# Focuser.net
KiCad netlist of a schematic drawn in EAGLE
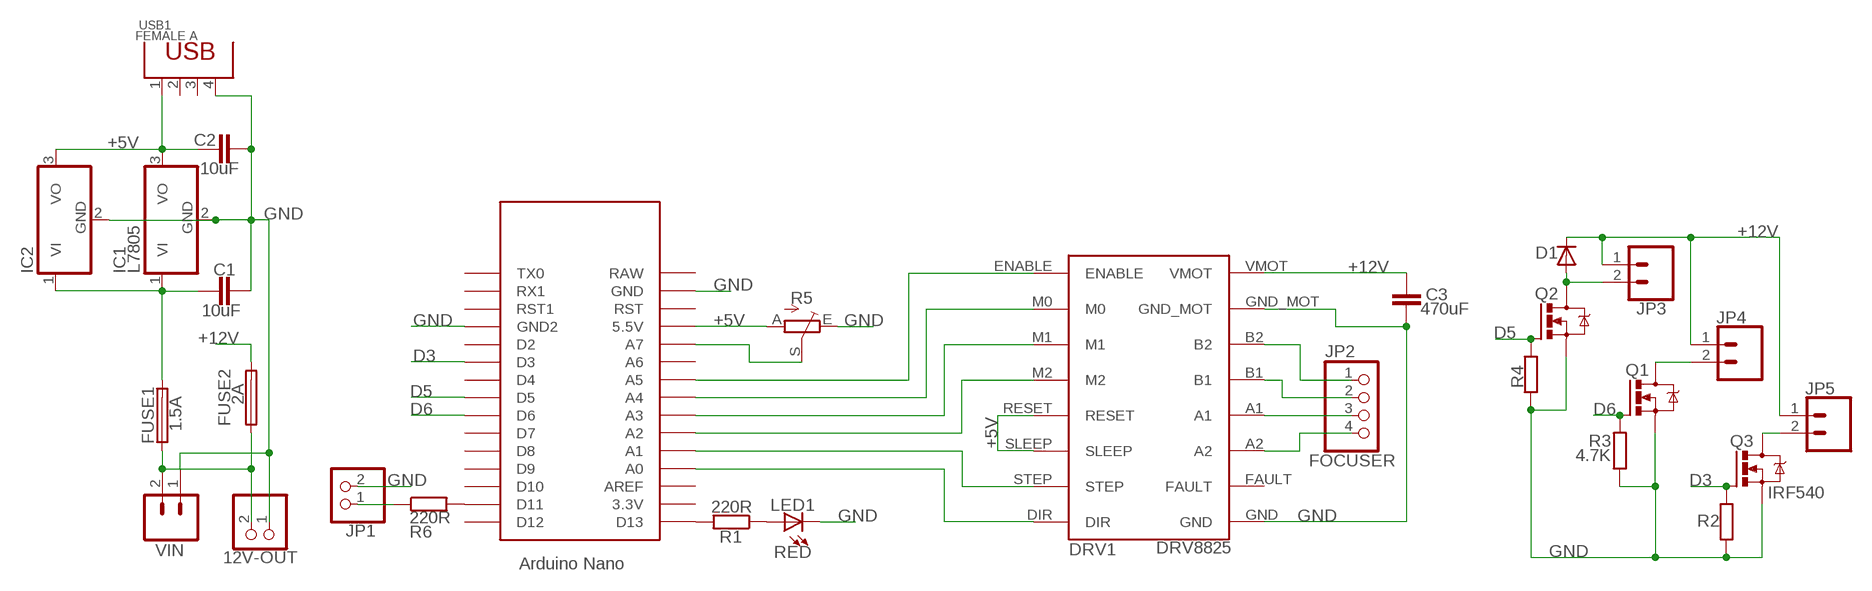
[diagram p0: schematic, sheet 1]

(export (version "E")
  (design (tool "Eeschema 10.0.6"))
  (components
    (comp (ref "12V-OUT")
      (value "PINHD-1X2")
      (footprint "eagle-import:1X02")
      (libsource (lib "eagle-import") (part "PINHD-1X2"))
    )
    (comp (ref "C1")
      (value "10uF")
      (footprint "eagle-import:C025-024X044")
      (libsource (lib "eagle-import") (part "C-EU025-024X044"))
    )
    (comp (ref "C2")
      (value "10uF")
      (footprint "eagle-import:C025-024X044")
      (libsource (lib "eagle-import") (part "C-EU025-024X044"))
    )
    (comp (ref "C3")
      (value "470uF")
      (footprint "eagle-import:C5B2.5")
      (fields (field (name "SPICEPREFIX") "C"))
      (libsource (lib "eagle-import") (part "C5/2.5"))
    )
    (comp (ref "D1")
      (value "DIODE-D-2.5")
      (footprint "eagle-import:D-2.5")
      (libsource (lib "eagle-import") (part "DIODE-D-2.5"))
    )
    (comp (ref "DRV1")
      (value "DRV8825")
      (footprint "eagle-import:DRV8825")
      (fields (field (name "SPICEPREFIX") "X"))
      (libsource (lib "eagle-import") (part "DRV8825"))
    )
    (comp (ref "FUSE1")
      (value "1.5A")
      (footprint "eagle-import:FUSE_HOLDER_5X20MM")
      (libsource (lib "eagle-import") (part "FUSEBLANK_5X20MM"))
    )
    (comp (ref "FUSE2")
      (value "2A")
      (footprint "eagle-import:FUSE_HOLDER_5X20MM")
      (libsource (lib "eagle-import") (part "FUSEBLANK_5X20MM"))
    )
    (comp (ref "IC1")
      (value "L7805")
      (footprint "eagle-import:TO220V")
      (libsource (lib "eagle-import") (part "78TV6"))
    )
    (comp (ref "IC2")
      (value "L7805")
      (footprint "eagle-import:TO220V")
      (libsource (lib "eagle-import") (part "78TV6"))
    )
    (comp (ref "JP1")
      (value "PINHD-1X2")
      (footprint "eagle-import:1X02")
      (fields (field (name "SPICEPREFIX") "B"))
      (libsource (lib "eagle-import") (part "PINHD-1X2"))
    )
    (comp (ref "JP2")
      (value "FOCUSER")
      (footprint "eagle-import:1X04")
      (fields (field (name "SPICEPREFIX") "E"))
      (libsource (lib "eagle-import") (part "PINHD-1X4"))
    )
    (comp (ref "JP3")
      (value "CONN_025MM")
      (footprint "eagle-import:SCREWTERMINAL-5MM-2")
      (libsource (lib "eagle-import") (part "CONN_025MM"))
    )
    (comp (ref "JP4")
      (value "CONN_025MM")
      (footprint "eagle-import:SCREWTERMINAL-5MM-2")
      (libsource (lib "eagle-import") (part "CONN_025MM"))
    )
    (comp (ref "JP5")
      (value "CONN_025MM")
      (footprint "eagle-import:SCREWTERMINAL-5MM-2")
      (fields (field (name "SPICEPREFIX") "H"))
      (libsource (lib "eagle-import") (part "CONN_025MM"))
    )
    (comp (ref "LED1")
      (value "RED")
      (footprint "eagle-import:LED3MM")
      (fields (field (name "SPICEPREFIX") "L"))
      (libsource (lib "eagle-import") (part "LED3MM"))
    )
    (comp (ref "Q1")
      (value "IRF540")
      (footprint "eagle-import:TO220BV")
      (libsource (lib "eagle-import") (part "IRF540"))
    )
    (comp (ref "Q2")
      (value "IRF540")
      (footprint "eagle-import:TO220BV")
      (libsource (lib "eagle-import") (part "IRF540"))
    )
    (comp (ref "Q3")
      (value "IRF540")
      (footprint "eagle-import:TO220BV")
      (libsource (lib "eagle-import") (part "IRF540"))
    )
    (comp (ref "R1")
      (value "220R")
      (footprint "eagle-import:0204_5")
      (fields (field (name "SPICEPREFIX") "R"))
      (libsource (lib "eagle-import") (part "resistor_348_R-EU_0204/5"))
    )
    (comp (ref "R2")
      (value "4.7K")
      (footprint "eagle-import:0204_5")
      (libsource (lib "eagle-import") (part "R-EU_0204/5"))
    )
    (comp (ref "R3")
      (value "4.7K")
      (footprint "eagle-import:0204_5")
      (libsource (lib "eagle-import") (part "R-EU_0204/5"))
    )
    (comp (ref "R4")
      (value "4.7K")
      (footprint "eagle-import:0204_5")
      (libsource (lib "eagle-import") (part "R-EU_0204/5"))
    )
    (comp (ref "R5")
      (value "TRIM_EU-B64Y")
      (footprint "eagle-import:B64Y")
      (fields (field (name "SPICEPREFIX") "J"))
      (libsource (lib "eagle-import") (part "TRIM_EU-B64Y"))
    )
    (comp (ref "R6")
      (value "220R")
      (footprint "eagle-import:0204_5")
      (fields (field (name "SPICEPREFIX") "R"))
      (libsource (lib "eagle-import") (part "resistor_348_R-EU_0204/5"))
    )
    (comp (ref "U$1")
      (value "NANO")
      (footprint "eagle-import:NANO")
      (libsource (lib "eagle-import") (part "NANO"))
    )
    (comp (ref "USB1")
      (value "FEMALE A")
      (footprint "eagle-import:USB4+2P-2.0-90D")
      (libsource (lib "eagle-import") (part "DIP-USB-A-TYPE-FMAL(4+2P-2.0-90D)"))
    )
    (comp (ref "VIN")
      (value "CONN_025MM")
      (footprint "eagle-import:SCREWTERMINAL-5MM-2")
      (libsource (lib "eagle-import") (part "CONN_025MM"))
    )
  )
  (nets
    (net (code "1") (name "/+5V") (class "Default")
      (node (ref "C2") (pin "1") (pinfunction "1_1") (pintype "passive"))
      (node (ref "DRV1") (pin "RESET") (pinfunction "RESET_RESET") (pintype "bidirectional"))
      (node (ref "DRV1") (pin "SLEEP") (pinfunction "SLEEP_SLEEP") (pintype "bidirectional"))
      (node (ref "IC1") (pin "3") (pinfunction "VO_3") (pintype "passive"))
      (node (ref "IC2") (pin "3") (pinfunction "VO_3") (pintype "passive"))
      (node (ref "R5") (pin "A") (pinfunction "A_A") (pintype "passive"))
      (node (ref "U$1") (pin "5V") (pinfunction "5.5V_5V") (pintype "bidirectional"))
      (node (ref "USB1") (pin "1") (pinfunction "1_1") (pintype "bidirectional"))
    )
    (net (code "2") (name "/+12V") (class "Default")
      (node (ref "C3") (pin "2") (pinfunction "2_2") (pintype "passive"))
      (node (ref "D1") (pin "C") (pinfunction "C_C") (pintype "passive"))
      (node (ref "DRV1") (pin "VMOT") (pinfunction "VMOT_VMOT") (pintype "bidirectional"))
      (node (ref "FUSE2") (pin "2") (pinfunction "2_2") (pintype "passive"))
      (node (ref "JP3") (pin "1") (pinfunction "1_1") (pintype "passive"))
      (node (ref "JP4") (pin "1") (pinfunction "1_1") (pintype "passive"))
      (node (ref "JP5") (pin "1") (pinfunction "1_1") (pintype "passive"))
    )
    (net (code "3") (name "/D3") (class "Default")
      (node (ref "Q3") (pin "G") (pinfunction "G_G") (pintype "passive"))
      (node (ref "R2") (pin "2") (pinfunction "2_2") (pintype "passive"))
      (node (ref "U$1") (pin "D3") (pinfunction "D3_D3") (pintype "bidirectional"))
    )
    (net (code "4") (name "/D5") (class "Default")
      (node (ref "Q2") (pin "G") (pinfunction "G_G") (pintype "passive"))
      (node (ref "R4") (pin "2") (pinfunction "2_2") (pintype "passive"))
      (node (ref "U$1") (pin "D5") (pinfunction "D5_D5") (pintype "bidirectional"))
    )
    (net (code "5") (name "/D6") (class "Default")
      (node (ref "Q1") (pin "G") (pinfunction "G_G") (pintype "passive"))
      (node (ref "R3") (pin "2") (pinfunction "2_2") (pintype "passive"))
      (node (ref "U$1") (pin "D6") (pinfunction "D6_D6") (pintype "bidirectional"))
    )
    (net (code "6") (name "/GND") (class "Default")
      (node (ref "12V-OUT") (pin "1") (pinfunction "1_1") (pintype "passive"))
      (node (ref "C1") (pin "2") (pinfunction "2_2") (pintype "passive"))
      (node (ref "C2") (pin "2") (pinfunction "2_2") (pintype "passive"))
      (node (ref "C3") (pin "1") (pinfunction "1_1") (pintype "passive"))
      (node (ref "DRV1") (pin "GND") (pinfunction "GND_GND") (pintype "bidirectional"))
      (node (ref "DRV1") (pin "GND_MOT") (pinfunction "GND_MOT_GND_MOT") (pintype "bidirectional"))
      (node (ref "IC1") (pin "2") (pinfunction "GND_2") (pintype "passive"))
      (node (ref "IC2") (pin "2") (pinfunction "GND_2") (pintype "passive"))
      (node (ref "JP1") (pin "2") (pinfunction "2_2") (pintype "passive"))
      (node (ref "LED1") (pin "K") (pinfunction "C_K") (pintype "passive"))
      (node (ref "Q1") (pin "S") (pinfunction "S_S") (pintype "passive"))
      (node (ref "Q2") (pin "S") (pinfunction "S_S") (pintype "passive"))
      (node (ref "Q3") (pin "S") (pinfunction "S_S") (pintype "passive"))
      (node (ref "R2") (pin "1") (pinfunction "1_1") (pintype "passive"))
      (node (ref "R3") (pin "1") (pinfunction "1_1") (pintype "passive"))
      (node (ref "R4") (pin "1") (pinfunction "1_1") (pintype "passive"))
      (node (ref "R5") (pin "E") (pinfunction "E_E") (pintype "passive"))
      (node (ref "U$1") (pin "GND") (pinfunction "GND_GND") (pintype "bidirectional"))
      (node (ref "U$1") (pin "GND1") (pinfunction "GND2_GND1") (pintype "bidirectional"))
      (node (ref "USB1") (pin "4") (pinfunction "4_4") (pintype "bidirectional"))
      (node (ref "VIN") (pin "1") (pinfunction "1_1") (pintype "passive"))
    )
    (net (code "7") (name "Net-(12V-OUT-Pad2)") (class "Default")
      (node (ref "12V-OUT") (pin "2") (pinfunction "2_2") (pintype "passive"))
      (node (ref "FUSE1") (pin "1") (pinfunction "1_1") (pintype "passive"))
      (node (ref "FUSE2") (pin "1") (pinfunction "1_1") (pintype "passive"))
      (node (ref "VIN") (pin "2") (pinfunction "2_2") (pintype "passive"))
    )
    (net (code "8") (name "Net-(D1-PadA)") (class "Default")
      (node (ref "D1") (pin "A") (pinfunction "A_A") (pintype "passive"))
      (node (ref "JP3") (pin "2") (pinfunction "2_2") (pintype "passive"))
      (node (ref "Q2") (pin "D") (pinfunction "D_D") (pintype "passive"))
    )
    (net (code "9") (name "Net-(DRV1-PadA1)") (class "Default")
      (node (ref "DRV1") (pin "A1") (pinfunction "A1_A1") (pintype "bidirectional"))
      (node (ref "JP2") (pin "3") (pinfunction "3_3") (pintype "passive"))
    )
    (net (code "10") (name "Net-(DRV1-PadA2)") (class "Default")
      (node (ref "DRV1") (pin "A2") (pinfunction "A2_A2") (pintype "bidirectional"))
      (node (ref "JP2") (pin "4") (pinfunction "4_4") (pintype "passive"))
    )
    (net (code "11") (name "Net-(DRV1-PadB1)") (class "Default")
      (node (ref "DRV1") (pin "B1") (pinfunction "B1_B1") (pintype "bidirectional"))
      (node (ref "JP2") (pin "2") (pinfunction "2_2") (pintype "passive"))
    )
    (net (code "12") (name "Net-(DRV1-PadB2)") (class "Default")
      (node (ref "DRV1") (pin "B2") (pinfunction "B2_B2") (pintype "bidirectional"))
      (node (ref "JP2") (pin "1") (pinfunction "1_1") (pintype "passive"))
    )
    (net (code "13") (name "Net-(DRV1-PadDIR)") (class "Default")
      (node (ref "DRV1") (pin "DIR") (pinfunction "DIR_DIR") (pintype "bidirectional"))
      (node (ref "U$1") (pin "A0") (pinfunction "A0_A0") (pintype "bidirectional"))
    )
    (net (code "14") (name "Net-(DRV1-PadENABLE)") (class "Default")
      (node (ref "DRV1") (pin "ENABLE") (pinfunction "ENABLE_ENABLE") (pintype "bidirectional"))
      (node (ref "U$1") (pin "A5") (pinfunction "A5_A5") (pintype "bidirectional"))
    )
    (net (code "15") (name "Net-(DRV1-PadM0)") (class "Default")
      (node (ref "DRV1") (pin "M0") (pinfunction "M0_M0") (pintype "bidirectional"))
      (node (ref "U$1") (pin "A4") (pinfunction "A4_A4") (pintype "bidirectional"))
    )
    (net (code "16") (name "Net-(DRV1-PadM1)") (class "Default")
      (node (ref "DRV1") (pin "M1") (pinfunction "M1_M1") (pintype "bidirectional"))
      (node (ref "U$1") (pin "A3") (pinfunction "A3_A3") (pintype "bidirectional"))
    )
    (net (code "17") (name "Net-(DRV1-PadM2)") (class "Default")
      (node (ref "DRV1") (pin "M2") (pinfunction "M2_M2") (pintype "bidirectional"))
      (node (ref "U$1") (pin "A2") (pinfunction "A2_A2") (pintype "bidirectional"))
    )
    (net (code "18") (name "Net-(DRV1-PadSTEP)") (class "Default")
      (node (ref "DRV1") (pin "STEP") (pinfunction "STEP_STEP") (pintype "bidirectional"))
      (node (ref "U$1") (pin "A1") (pinfunction "A1_A1") (pintype "bidirectional"))
    )
    (net (code "19") (name "Net-(IC1-VI)") (class "Default")
      (node (ref "C1") (pin "1") (pinfunction "1_1") (pintype "passive"))
      (node (ref "FUSE1") (pin "2") (pinfunction "2_2") (pintype "passive"))
      (node (ref "IC1") (pin "1") (pinfunction "VI_1") (pintype "input"))
      (node (ref "IC2") (pin "1") (pinfunction "VI_1") (pintype "input"))
    )
    (net (code "20") (name "Net-(JP1-Pad1)") (class "Default")
      (node (ref "JP1") (pin "1") (pinfunction "1_1") (pintype "passive"))
      (node (ref "R6") (pin "1") (pinfunction "1_1") (pintype "passive"))
    )
    (net (code "21") (name "Net-(JP4-Pad2)") (class "Default")
      (node (ref "JP4") (pin "2") (pinfunction "2_2") (pintype "passive"))
      (node (ref "Q1") (pin "D") (pinfunction "D_D") (pintype "passive"))
    )
    (net (code "22") (name "Net-(JP5-Pad2)") (class "Default")
      (node (ref "JP5") (pin "2") (pinfunction "2_2") (pintype "passive"))
      (node (ref "Q3") (pin "D") (pinfunction "D_D") (pintype "passive"))
    )
    (net (code "23") (name "Net-(LED1-PadA)") (class "Default")
      (node (ref "LED1") (pin "A") (pinfunction "A_A") (pintype "passive"))
      (node (ref "R1") (pin "1") (pinfunction "1_1") (pintype "passive"))
    )
    (net (code "24") (name "Net-(R1-Pad2)") (class "Default")
      (node (ref "R1") (pin "2") (pinfunction "2_2") (pintype "passive"))
      (node (ref "U$1") (pin "D13") (pinfunction "D13_D13") (pintype "bidirectional"))
    )
    (net (code "25") (name "Net-(R5-PadS)") (class "Default")
      (node (ref "R5") (pin "S") (pinfunction "S_S") (pintype "passive"))
      (node (ref "U$1") (pin "A7") (pinfunction "A7_A7") (pintype "bidirectional"))
    )
    (net (code "26") (name "Net-(R6-Pad2)") (class "Default")
      (node (ref "R6") (pin "2") (pinfunction "2_2") (pintype "passive"))
      (node (ref "U$1") (pin "D11") (pinfunction "D11_D11") (pintype "bidirectional"))
    )
    (net (code "27") (name "unconnected-(DRV1-PadFAULT)") (class "Default")
      (node (ref "DRV1") (pin "FAULT") (pinfunction "FAULT_FAULT") (pintype "bidirectional"))
    )
    (net (code "28") (name "unconnected-(U$1-Pad3.3V)") (class "Default")
      (node (ref "U$1") (pin "3.3V") (pinfunction "3.3V_3.3V") (pintype "bidirectional"))
    )
    (net (code "29") (name "unconnected-(U$1-PadA6)") (class "Default")
      (node (ref "U$1") (pin "A6") (pinfunction "A6_A6") (pintype "bidirectional"))
    )
    (net (code "30") (name "unconnected-(U$1-PadAREF)") (class "Default")
      (node (ref "U$1") (pin "AREF") (pinfunction "AREF_AREF") (pintype "bidirectional"))
    )
    (net (code "31") (name "unconnected-(U$1-PadD2)") (class "Default")
      (node (ref "U$1") (pin "D2") (pinfunction "D2_D2") (pintype "bidirectional"))
    )
    (net (code "32") (name "unconnected-(U$1-PadD4)") (class "Default")
      (node (ref "U$1") (pin "D4") (pinfunction "D4_D4") (pintype "bidirectional"))
    )
    (net (code "33") (name "unconnected-(U$1-PadD7)") (class "Default")
      (node (ref "U$1") (pin "D7") (pinfunction "D7_D7") (pintype "bidirectional"))
    )
    (net (code "34") (name "unconnected-(U$1-PadD8)") (class "Default")
      (node (ref "U$1") (pin "D8") (pinfunction "D8_D8") (pintype "bidirectional"))
    )
    (net (code "35") (name "unconnected-(U$1-PadD9)") (class "Default")
      (node (ref "U$1") (pin "D9") (pinfunction "D9_D9") (pintype "bidirectional"))
    )
    (net (code "36") (name "unconnected-(U$1-PadD10)") (class "Default")
      (node (ref "U$1") (pin "D10") (pinfunction "D10_D10") (pintype "bidirectional"))
    )
    (net (code "37") (name "unconnected-(U$1-PadD12)") (class "Default")
      (node (ref "U$1") (pin "D12") (pinfunction "D12_D12") (pintype "bidirectional"))
    )
    (net (code "38") (name "unconnected-(U$1-PadICSP1)") (class "Default")
      (node (ref "U$1") (pin "ICSP1") (pinfunction "ICSP1_ICSP1") (pintype "bidirectional"))
    )
    (net (code "39") (name "unconnected-(U$1-PadICSP2)") (class "Default")
      (node (ref "U$1") (pin "ICSP2") (pinfunction "ICSP2_ICSP2") (pintype "bidirectional"))
    )
    (net (code "40") (name "unconnected-(U$1-PadICSP3)") (class "Default")
      (node (ref "U$1") (pin "ICSP3") (pinfunction "ICSP3_ICSP3") (pintype "bidirectional"))
    )
    (net (code "41") (name "unconnected-(U$1-PadICSP4)") (class "Default")
      (node (ref "U$1") (pin "ICSP4") (pinfunction "ICSP4_ICSP4") (pintype "bidirectional"))
    )
    (net (code "42") (name "unconnected-(U$1-PadICSP5)") (class "Default")
      (node (ref "U$1") (pin "ICSP5") (pinfunction "ICSP5_ICSP5") (pintype "bidirectional"))
    )
    (net (code "43") (name "unconnected-(U$1-PadICSP6)") (class "Default")
      (node (ref "U$1") (pin "ICSP6") (pinfunction "ICSP6_ICSP6") (pintype "bidirectional"))
    )
    (net (code "44") (name "unconnected-(U$1-PadRAW)") (class "Default")
      (node (ref "U$1") (pin "RAW") (pinfunction "RAW_RAW") (pintype "bidirectional"))
    )
    (net (code "45") (name "unconnected-(U$1-PadRST)") (class "Default")
      (node (ref "U$1") (pin "RST") (pinfunction "RST_RST") (pintype "bidirectional"))
    )
    (net (code "46") (name "unconnected-(U$1-PadRST1)") (class "Default")
      (node (ref "U$1") (pin "RST1") (pinfunction "RST1_RST1") (pintype "bidirectional"))
    )
    (net (code "47") (name "unconnected-(U$1-PadRX1)") (class "Default")
      (node (ref "U$1") (pin "RX1") (pinfunction "RX1_RX1") (pintype "bidirectional"))
    )
    (net (code "48") (name "unconnected-(U$1-PadTX0)") (class "Default")
      (node (ref "U$1") (pin "TX0") (pinfunction "TX0_TX0") (pintype "bidirectional"))
    )
    (net (code "49") (name "unconnected-(USB1-Pad2)") (class "Default")
      (node (ref "USB1") (pin "2") (pinfunction "2_2") (pintype "bidirectional"))
    )
    (net (code "50") (name "unconnected-(USB1-Pad3)") (class "Default")
      (node (ref "USB1") (pin "3") (pinfunction "3_3") (pintype "bidirectional"))
    )
  )
)
